# Sheet4.net
KiCad netlist of a schematic drawn in Altium Designer
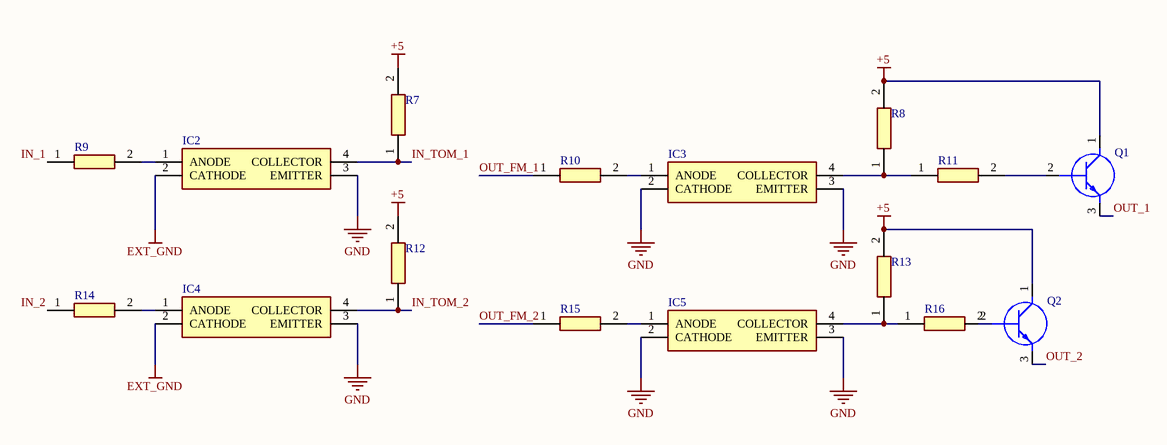
[diagram p0: Sheet4.SchDoc]

(export (version "E")
  (design (tool "Eeschema 10.0.6"))
  (components
    (comp (ref "IC2")
      (value "PC817X2NSZ0F")
      (footprint "SamacSys:DIP762W60P254L458H400Q4N")
      (description "Integrated Circuit")
      (libsource (lib "*") (part "PC817X2NSZ0F"))
    )
    (comp (ref "IC3")
      (value "PC817X2NSZ0F")
      (footprint "SamacSys:DIP762W60P254L458H400Q4N")
      (description "Integrated Circuit")
      (libsource (lib "*") (part "PC817X2NSZ0F"))
    )
    (comp (ref "IC4")
      (value "PC817X2NSZ0F")
      (footprint "SamacSys:DIP762W60P254L458H400Q4N")
      (description "Integrated Circuit")
      (libsource (lib "*") (part "PC817X2NSZ0F"))
    )
    (comp (ref "IC5")
      (value "PC817X2NSZ0F")
      (footprint "SamacSys:DIP762W60P254L458H400Q4N")
      (description "Integrated Circuit")
      (libsource (lib "*") (part "PC817X2NSZ0F"))
    )
    (comp (ref "Q1")
      (value "BC547BG")
      (footprint "SamacSys:TO-92_(TO-226)")
      (description "Transistor BJT NPN")
      (libsource (lib "*") (part "BC547BG"))
    )
    (comp (ref "Q2")
      (value "BC547BG")
      (footprint "SamacSys:TO-92_(TO-226)")
      (description "Transistor BJT NPN")
      (libsource (lib "*") (part "BC547BG"))
    )
    (comp (ref "R7")
      (value "RN73C2A10KLTDF")
      (footprint "SamacSys:RESC2012X65N")
      (description "Resistor")
      (fields (field (name "MOUSER PART NUMBER") "279-RN73C2A10KLTDF"))
      (libsource (lib "*") (part "RN73C2A10KLTDF"))
    )
    (comp (ref "R8")
      (value "RN73C2A10KLTDF")
      (footprint "SamacSys:RESC2012X65N")
      (description "Resistor")
      (fields (field (name "MOUSER PART NUMBER") "279-RN73C2A10KLTDF"))
      (libsource (lib "*") (part "RN73C2A10KLTDF"))
    )
    (comp (ref "R9")
      (value "PCF0805R-1K0BI")
      (footprint "SamacSys:RESC2012X65N")
      (description "Resistor")
      (fields (field (name "MOUSER PART NUMBER") "756-PCF0805R1K0BI"))
      (libsource (lib "*") (part "PCF0805R-1K0BI"))
    )
    (comp (ref "R10")
      (value "PCF0805R-1K0BI")
      (footprint "SamacSys:RESC2012X65N")
      (description "Resistor")
      (fields (field (name "MOUSER PART NUMBER") "756-PCF0805R1K0BI"))
      (libsource (lib "*") (part "PCF0805R-1K0BI"))
    )
    (comp (ref "R11")
      (value "PCF0805R-1K0BI")
      (footprint "SamacSys:RESC2012X65N")
      (description "Resistor")
      (fields (field (name "MOUSER PART NUMBER") "756-PCF0805R1K0BI"))
      (libsource (lib "*") (part "PCF0805R-1K0BI"))
    )
    (comp (ref "R12")
      (value "RN73C2A10KLTDF")
      (footprint "SamacSys:RESC2012X65N")
      (description "Resistor")
      (fields (field (name "MOUSER PART NUMBER") "279-RN73C2A10KLTDF"))
      (libsource (lib "*") (part "RN73C2A10KLTDF"))
    )
    (comp (ref "R13")
      (value "RN73C2A10KLTDF")
      (footprint "SamacSys:RESC2012X65N")
      (description "Resistor")
      (fields (field (name "MOUSER PART NUMBER") "279-RN73C2A10KLTDF"))
      (libsource (lib "*") (part "RN73C2A10KLTDF"))
    )
    (comp (ref "R14")
      (value "PCF0805R-1K0BI")
      (footprint "SamacSys:RESC2012X65N")
      (description "Resistor")
      (fields (field (name "MOUSER PART NUMBER") "756-PCF0805R1K0BI"))
      (libsource (lib "*") (part "PCF0805R-1K0BI"))
    )
    (comp (ref "R15")
      (value "PCF0805R-1K0BI")
      (footprint "SamacSys:RESC2012X65N")
      (description "Resistor")
      (fields (field (name "MOUSER PART NUMBER") "756-PCF0805R1K0BI"))
      (libsource (lib "*") (part "PCF0805R-1K0BI"))
    )
    (comp (ref "R16")
      (value "PCF0805R-1K0BI")
      (footprint "SamacSys:RESC2012X65N")
      (description "Resistor")
      (fields (field (name "MOUSER PART NUMBER") "756-PCF0805R1K0BI"))
      (libsource (lib "*") (part "PCF0805R-1K0BI"))
    )
  )
  (nets
    (net (code "1") (name "+5") (class "Default")
      (node (ref "Q1") (pin "1") (pinfunction "C_1") (pintype "passive"))
      (node (ref "Q2") (pin "1") (pinfunction "C_1") (pintype "passive"))
      (node (ref "R12") (pin "2") (pinfunction "2_2") (pintype "passive"))
      (node (ref "R13") (pin "2") (pinfunction "2_2") (pintype "passive"))
      (node (ref "R7") (pin "2") (pinfunction "2_2") (pintype "passive"))
      (node (ref "R8") (pin "2") (pinfunction "2_2") (pintype "passive"))
    )
    (net (code "2") (name "/IN_1") (class "Default")
      (node (ref "R9") (pin "1") (pinfunction "1_1") (pintype "passive"))
    )
    (net (code "3") (name "/IN_2") (class "Default")
      (node (ref "R14") (pin "1") (pinfunction "1_1") (pintype "passive"))
    )
    (net (code "4") (name "/IN_TOM_1") (class "Default")
      (node (ref "IC2") (pin "4") (pinfunction "COLLECTOR_4") (pintype "passive"))
      (node (ref "R7") (pin "1") (pinfunction "1_1") (pintype "passive"))
    )
    (net (code "5") (name "/IN_TOM_2") (class "Default")
      (node (ref "IC4") (pin "4") (pinfunction "COLLECTOR_4") (pintype "passive"))
      (node (ref "R12") (pin "1") (pinfunction "1_1") (pintype "passive"))
    )
    (net (code "6") (name "/OUT_1") (class "Default")
      (node (ref "Q1") (pin "3") (pinfunction "E_3") (pintype "passive"))
    )
    (net (code "7") (name "/OUT_2") (class "Default")
      (node (ref "Q2") (pin "3") (pinfunction "E_3") (pintype "passive"))
    )
    (net (code "8") (name "/OUT_FM_1") (class "Default")
      (node (ref "R10") (pin "1") (pinfunction "1_1") (pintype "passive"))
    )
    (net (code "9") (name "/OUT_FM_2") (class "Default")
      (node (ref "R15") (pin "1") (pinfunction "1_1") (pintype "passive"))
    )
    (net (code "10") (name "EXT_GND") (class "Default")
      (node (ref "IC2") (pin "2") (pinfunction "CATHODE_2") (pintype "passive"))
      (node (ref "IC4") (pin "2") (pinfunction "CATHODE_2") (pintype "passive"))
    )
    (net (code "11") (name "GND") (class "Default")
      (node (ref "IC2") (pin "3") (pinfunction "EMITTER_3") (pintype "passive"))
      (node (ref "IC3") (pin "2") (pinfunction "CATHODE_2") (pintype "passive"))
      (node (ref "IC3") (pin "3") (pinfunction "EMITTER_3") (pintype "passive"))
      (node (ref "IC4") (pin "3") (pinfunction "EMITTER_3") (pintype "passive"))
      (node (ref "IC5") (pin "2") (pinfunction "CATHODE_2") (pintype "passive"))
      (node (ref "IC5") (pin "3") (pinfunction "EMITTER_3") (pintype "passive"))
    )
    (net (code "12") (name "Net-(IC2-ANODE)") (class "Default")
      (node (ref "IC2") (pin "1") (pinfunction "ANODE_1") (pintype "passive"))
      (node (ref "R9") (pin "2") (pinfunction "2_2") (pintype "passive"))
    )
    (net (code "13") (name "Net-(IC3-ANODE)") (class "Default")
      (node (ref "IC3") (pin "1") (pinfunction "ANODE_1") (pintype "passive"))
      (node (ref "R10") (pin "2") (pinfunction "2_2") (pintype "passive"))
    )
    (net (code "14") (name "Net-(IC3-COLLECTOR)") (class "Default")
      (node (ref "IC3") (pin "4") (pinfunction "COLLECTOR_4") (pintype "passive"))
      (node (ref "R11") (pin "1") (pinfunction "1_1") (pintype "passive"))
      (node (ref "R8") (pin "1") (pinfunction "1_1") (pintype "passive"))
    )
    (net (code "15") (name "Net-(IC4-ANODE)") (class "Default")
      (node (ref "IC4") (pin "1") (pinfunction "ANODE_1") (pintype "passive"))
      (node (ref "R14") (pin "2") (pinfunction "2_2") (pintype "passive"))
    )
    (net (code "16") (name "Net-(IC5-ANODE)") (class "Default")
      (node (ref "IC5") (pin "1") (pinfunction "ANODE_1") (pintype "passive"))
      (node (ref "R15") (pin "2") (pinfunction "2_2") (pintype "passive"))
    )
    (net (code "17") (name "Net-(IC5-COLLECTOR)") (class "Default")
      (node (ref "IC5") (pin "4") (pinfunction "COLLECTOR_4") (pintype "passive"))
      (node (ref "R13") (pin "1") (pinfunction "1_1") (pintype "passive"))
      (node (ref "R16") (pin "1") (pinfunction "1_1") (pintype "passive"))
    )
    (net (code "18") (name "Net-(Q1-B)") (class "Default")
      (node (ref "Q1") (pin "2") (pinfunction "B_2") (pintype "passive"))
      (node (ref "R11") (pin "2") (pinfunction "2_2") (pintype "passive"))
    )
    (net (code "19") (name "Net-(Q2-B)") (class "Default")
      (node (ref "Q2") (pin "2") (pinfunction "B_2") (pintype "passive"))
      (node (ref "R16") (pin "2") (pinfunction "2_2") (pintype "passive"))
    )
  )
)
